# Motion_Driver_v2.net
KiCad netlist of a schematic drawn in Altium Designer
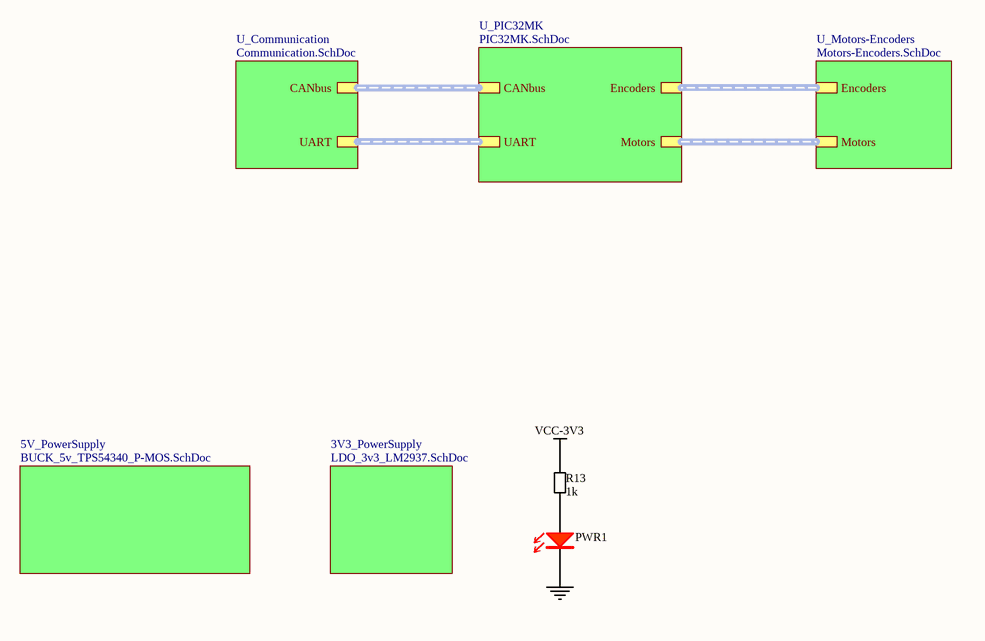
[diagram p0: Motion_Driver_v2.SchDoc]

(export (version "E")
  (design (tool "Eeschema 10.0.6"))
  (components
    (comp (ref "PWR1")
      (value "LED RED")
      (footprint "LED_RED_0805")
      (description "LED RED 0805")
      (fields
        (field (name "MANUFACTURER") "BRIGHT LED ELECTRONICS")
        (field (name "MANUFACTURER PART NUMBER") "BL-HUB35A-AV-TRB")
      )
      (libsource (lib "Discrete_Semiconductor") (part "LED_RED_0805"))
    )
    (comp (ref "R13")
      (value "1k")
      (footprint "RESC2013X38N-0805-NOOVERLAY")
      (description "RES SMD 1 kOhm 1/8W 0805")
      (fields (field (name "POWER") "0.125W, 1/8W"))
      (libsource (lib "Resistors") (part "00001001"))
    )
  )
  (nets
    (net (code "5") (name "GND") (class "Default")
      (node (ref "PWR1") (pin "1") (pinfunction "C_1") (pintype "passive"))
    )
    (net (code "6") (name "Net-(PWR1-A)") (class "Default")
      (node (ref "PWR1") (pin "2") (pinfunction "A_2") (pintype "passive"))
      (node (ref "R13") (pin "1") (pinfunction "1_1") (pintype "passive"))
    )
    (net (code "7") (name "VCC-3V3") (class "Default")
      (node (ref "R13") (pin "2") (pinfunction "2_2") (pintype "passive"))
    )
  )
)
